# berry_4_0.net
KiCad netlist of a schematic drawn in EAGLE
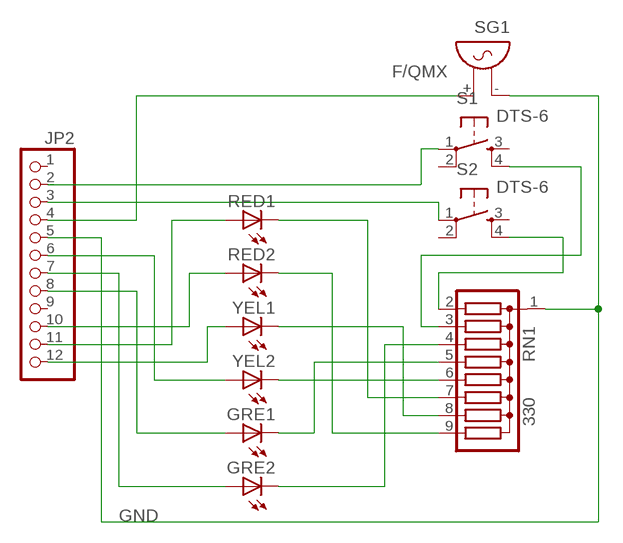
[diagram p0: schematic, sheet 1]

(export (version "E")
  (design (tool "Eeschema 10.0.6"))
  (components
    (comp (ref "GRE1")
      (value "LED3MM")
      (footprint "eagle-import:LED3MM")
      (libsource (lib "eagle-import") (part "LED3MM"))
    )
    (comp (ref "GRE2")
      (value "LED3MM")
      (footprint "eagle-import:LED3MM")
      (libsource (lib "eagle-import") (part "LED3MM"))
    )
    (comp (ref "JP2")
      (value "PINHD-1X12")
      (footprint "eagle-import:1X12")
      (libsource (lib "eagle-import") (part "PINHD-1X12"))
    )
    (comp (ref "RED1")
      (value "LED3MM")
      (footprint "eagle-import:LED3MM")
      (libsource (lib "eagle-import") (part "LED3MM"))
    )
    (comp (ref "RED2")
      (value "LED3MM")
      (footprint "eagle-import:LED3MM")
      (libsource (lib "eagle-import") (part "LED3MM"))
    )
    (comp (ref "RN1")
      (value "330")
      (footprint "eagle-import:SIL9")
      (libsource (lib "eagle-import") (part "G08R"))
    )
    (comp (ref "S1")
      (value "DTS-6")
      (footprint "eagle-import:DTS-6")
      (libsource (lib "eagle-import") (part "DTS-6"))
    )
    (comp (ref "S2")
      (value "DTS-6")
      (footprint "eagle-import:DTS-6")
      (libsource (lib "eagle-import") (part "DTS-6"))
    )
    (comp (ref "SG1")
      (value "F/QMX")
      (footprint "eagle-import:F_QMX")
      (libsource (lib "eagle-import") (part "F/QMX"))
    )
    (comp (ref "YEL1")
      (value "LED3MM")
      (footprint "eagle-import:LED3MM")
      (libsource (lib "eagle-import") (part "LED3MM"))
    )
    (comp (ref "YEL2")
      (value "LED3MM")
      (footprint "eagle-import:LED3MM")
      (libsource (lib "eagle-import") (part "LED3MM"))
    )
  )
  (nets
    (net (code "1") (name "/GND") (class "Default")
      (node (ref "JP2") (pin "5") (pinfunction "5_5") (pintype "passive"))
      (node (ref "RN1") (pin "1") (pinfunction "1_1") (pintype "passive"))
      (node (ref "SG1") (pin "-") (pinfunction "1_-") (pintype "passive"))
    )
    (net (code "2") (name "Net-(GRE1-C)") (class "Default")
      (node (ref "GRE1") (pin "K") (pinfunction "C_K") (pintype "passive"))
      (node (ref "RN1") (pin "5") (pinfunction "5_5") (pintype "passive"))
    )
    (net (code "3") (name "Net-(GRE1-PadA)") (class "Default")
      (node (ref "GRE1") (pin "A") (pinfunction "A_A") (pintype "passive"))
      (node (ref "JP2") (pin "8") (pinfunction "8_8") (pintype "passive"))
    )
    (net (code "4") (name "Net-(GRE2-C)") (class "Default")
      (node (ref "GRE2") (pin "K") (pinfunction "C_K") (pintype "passive"))
      (node (ref "RN1") (pin "4") (pinfunction "4_4") (pintype "passive"))
    )
    (net (code "5") (name "Net-(GRE2-PadA)") (class "Default")
      (node (ref "GRE2") (pin "A") (pinfunction "A_A") (pintype "passive"))
      (node (ref "JP2") (pin "7") (pinfunction "7_7") (pintype "passive"))
    )
    (net (code "6") (name "Net-(JP2-Pad2)") (class "Default")
      (node (ref "JP2") (pin "2") (pinfunction "2_2") (pintype "passive"))
      (node (ref "S1") (pin "1") (pinfunction "1_1") (pintype "passive"))
    )
    (net (code "7") (name "Net-(JP2-Pad3)") (class "Default")
      (node (ref "JP2") (pin "3") (pinfunction "3_3") (pintype "passive"))
      (node (ref "S2") (pin "1") (pinfunction "1_1") (pintype "passive"))
    )
    (net (code "8") (name "Net-(JP2-Pad6)") (class "Default")
      (node (ref "JP2") (pin "6") (pinfunction "6_6") (pintype "passive"))
      (node (ref "YEL2") (pin "A") (pinfunction "A_A") (pintype "passive"))
    )
    (net (code "9") (name "Net-(JP2-Pad10)") (class "Default")
      (node (ref "JP2") (pin "10") (pinfunction "10_10") (pintype "passive"))
      (node (ref "RED2") (pin "A") (pinfunction "A_A") (pintype "passive"))
    )
    (net (code "10") (name "Net-(JP2-Pad11)") (class "Default")
      (node (ref "JP2") (pin "11") (pinfunction "11_11") (pintype "passive"))
      (node (ref "RED1") (pin "A") (pinfunction "A_A") (pintype "passive"))
    )
    (net (code "11") (name "Net-(JP2-Pad12)") (class "Default")
      (node (ref "JP2") (pin "12") (pinfunction "12_12") (pintype "passive"))
      (node (ref "YEL1") (pin "A") (pinfunction "A_A") (pintype "passive"))
    )
    (net (code "12") (name "Net-(RED1-C)") (class "Default")
      (node (ref "RED1") (pin "K") (pinfunction "C_K") (pintype "passive"))
      (node (ref "RN1") (pin "7") (pinfunction "7_7") (pintype "passive"))
    )
    (net (code "13") (name "Net-(RED2-C)") (class "Default")
      (node (ref "RED2") (pin "K") (pinfunction "C_K") (pintype "passive"))
      (node (ref "RN1") (pin "9") (pinfunction "9_9") (pintype "passive"))
    )
    (net (code "14") (name "Net-(RN1-Pad2)") (class "Default")
      (node (ref "RN1") (pin "2") (pinfunction "2_2") (pintype "passive"))
      (node (ref "S2") (pin "4") (pinfunction "4_4") (pintype "passive"))
    )
    (net (code "15") (name "Net-(RN1-Pad3)") (class "Default")
      (node (ref "RN1") (pin "3") (pinfunction "3_3") (pintype "passive"))
      (node (ref "S1") (pin "4") (pinfunction "4_4") (pintype "passive"))
    )
    (net (code "16") (name "Net-(SG1-2)") (class "Default")
      (node (ref "JP2") (pin "4") (pinfunction "4_4") (pintype "passive"))
      (node (ref "SG1") (pin "+") (pinfunction "2_+") (pintype "passive"))
    )
    (net (code "17") (name "Net-(YEL1-C)") (class "Default")
      (node (ref "RN1") (pin "8") (pinfunction "8_8") (pintype "passive"))
      (node (ref "YEL1") (pin "K") (pinfunction "C_K") (pintype "passive"))
    )
    (net (code "18") (name "Net-(YEL2-C)") (class "Default")
      (node (ref "RN1") (pin "6") (pinfunction "6_6") (pintype "passive"))
      (node (ref "YEL2") (pin "K") (pinfunction "C_K") (pintype "passive"))
    )
    (net (code "19") (name "unconnected-(JP2-Pad1)") (class "Default")
      (node (ref "JP2") (pin "1") (pinfunction "1_1") (pintype "passive"))
    )
    (net (code "20") (name "unconnected-(JP2-Pad9)") (class "Default")
      (node (ref "JP2") (pin "9") (pinfunction "9_9") (pintype "passive"))
    )
    (net (code "21") (name "unconnected-(S1-Pad2)") (class "Default")
      (node (ref "S1") (pin "2") (pinfunction "2_2") (pintype "passive"))
    )
    (net (code "22") (name "unconnected-(S1-Pad3)") (class "Default")
      (node (ref "S1") (pin "3") (pinfunction "3_3") (pintype "passive"))
    )
    (net (code "23") (name "unconnected-(S2-Pad2)") (class "Default")
      (node (ref "S2") (pin "2") (pinfunction "2_2") (pintype "passive"))
    )
    (net (code "24") (name "unconnected-(S2-Pad3)") (class "Default")
      (node (ref "S2") (pin "3") (pinfunction "3_3") (pintype "passive"))
    )
  )
)
